# schematic_tab.net
KiCad netlist of a schematic drawn in EasyEDA
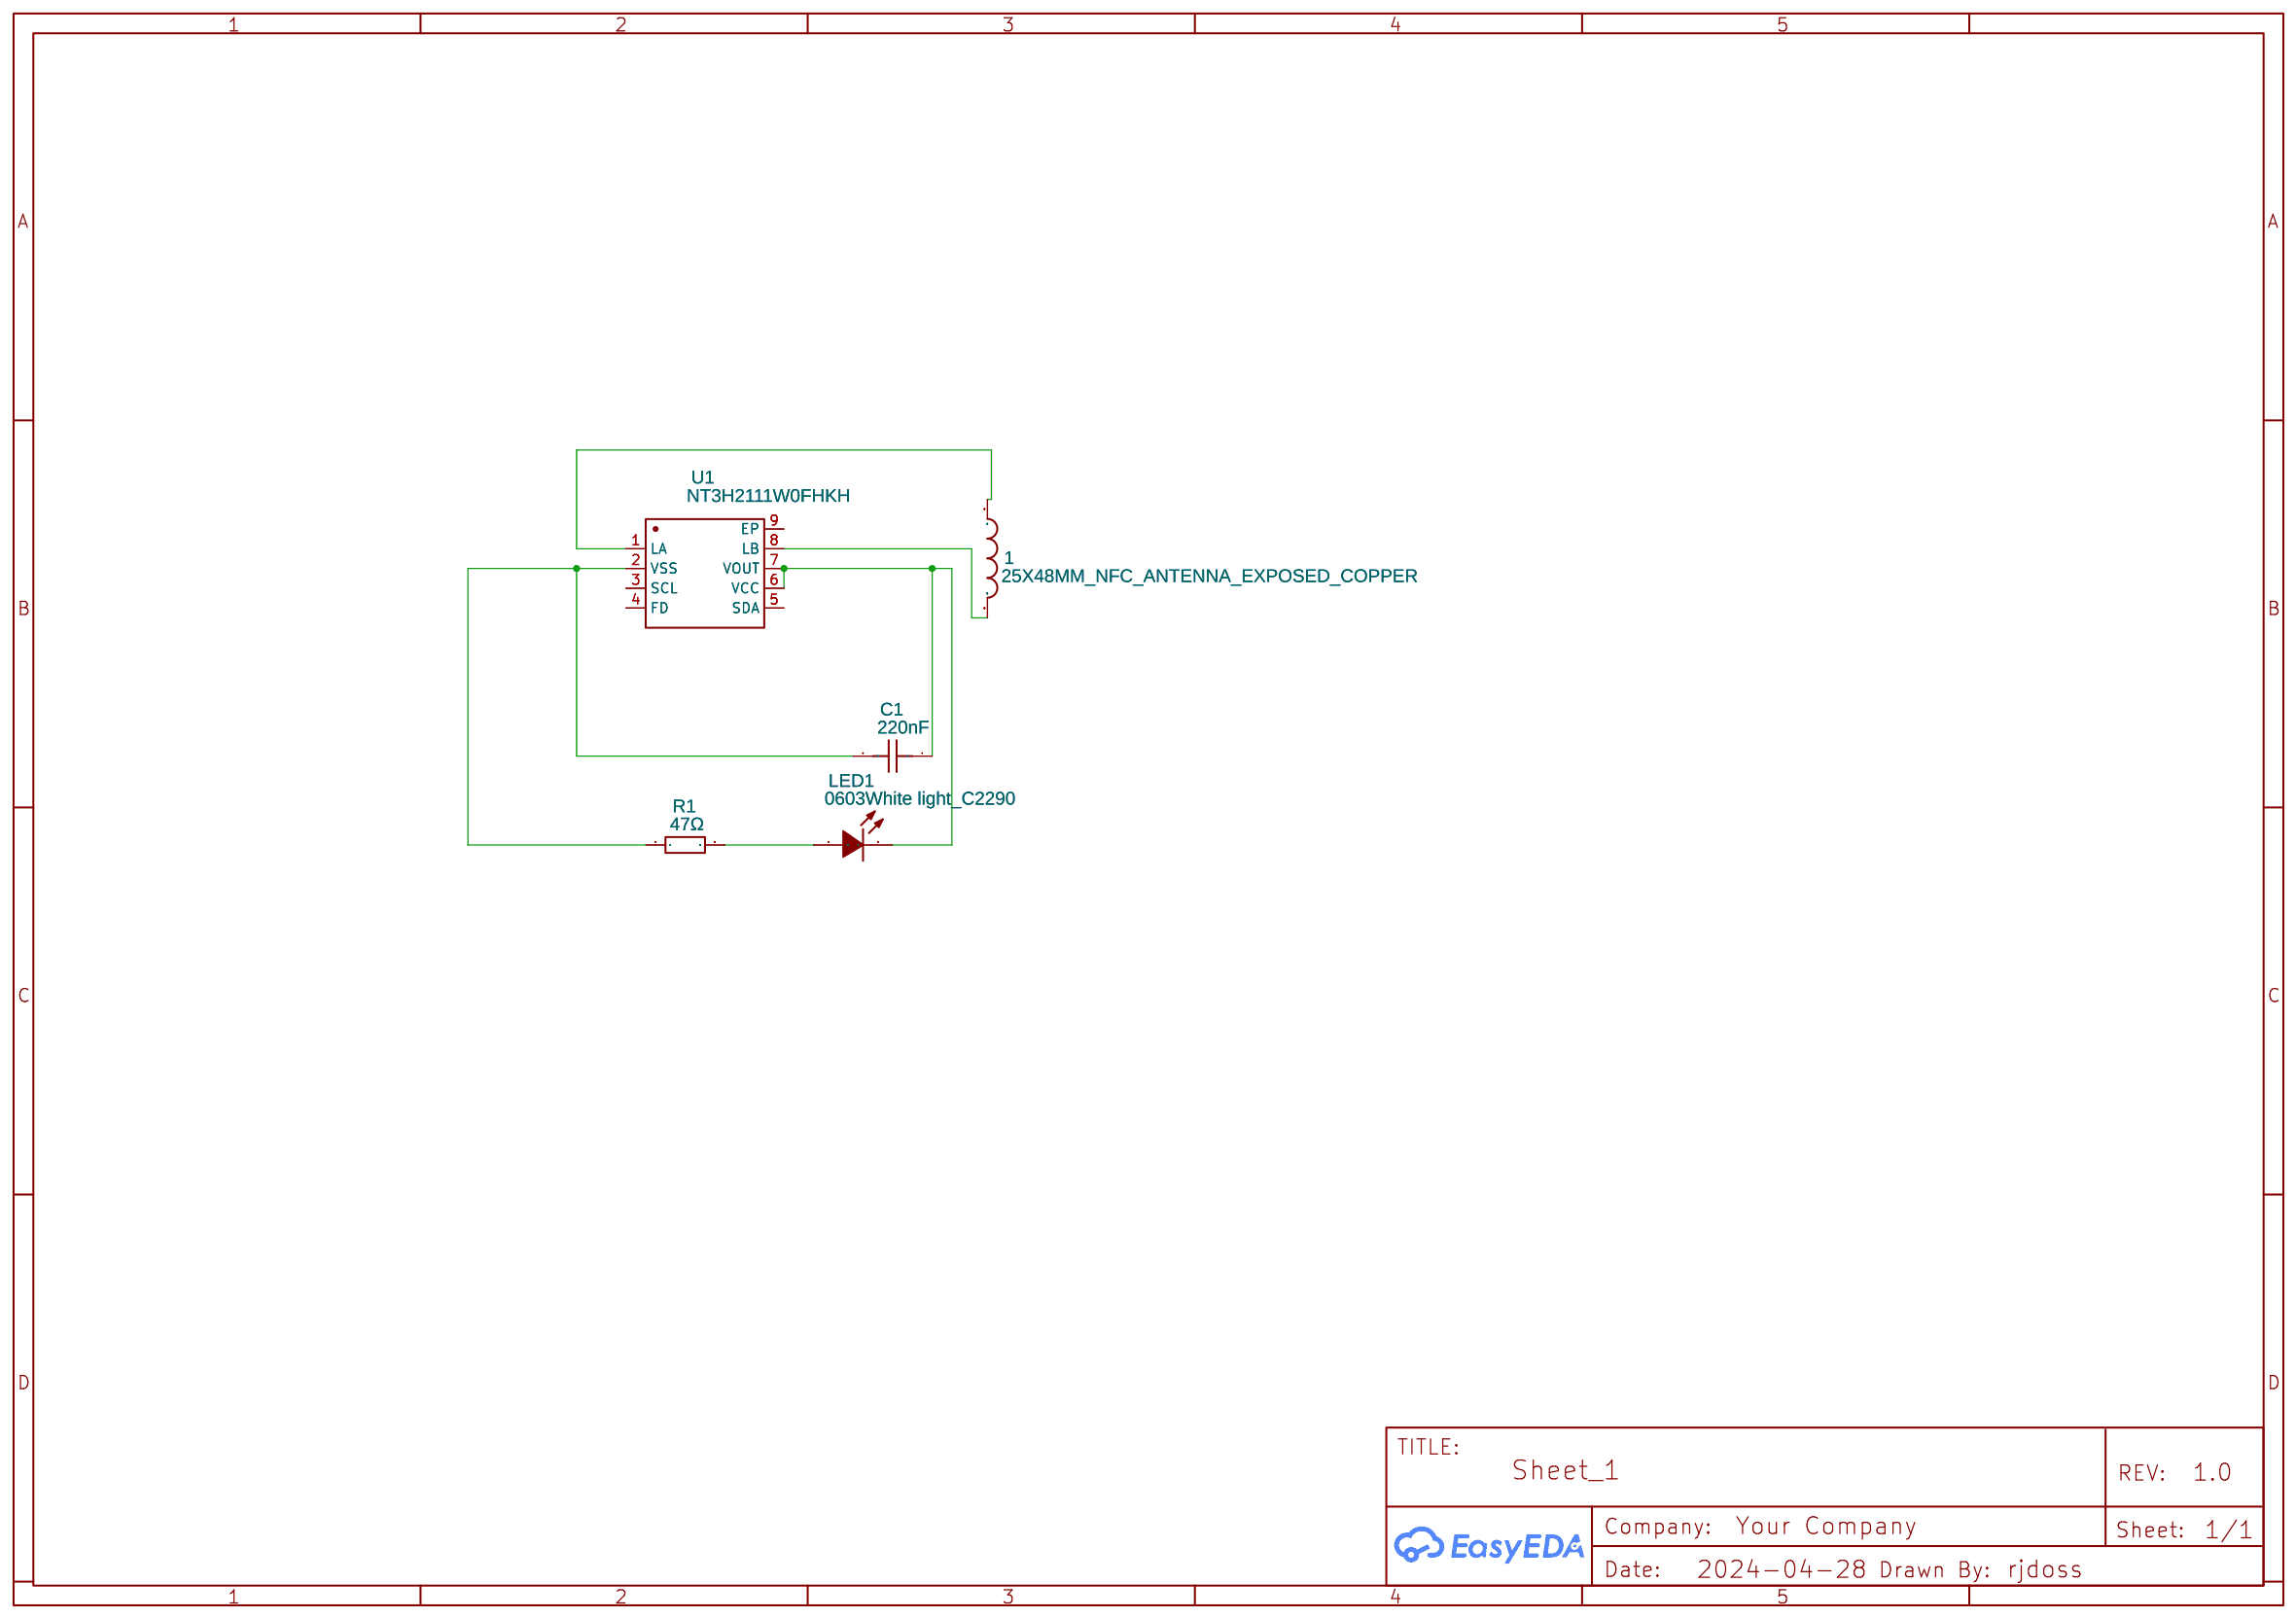
[diagram p0: schematic sheet]

(export (version "E")
  (design (tool "Eeschema 10.0.6"))
  (components
    (comp (ref "1")
      (value "25X48MM_NFC_ANTENNA_EXPOSED_COPPER")
      (libsource (lib "") (part "25X48MM_NFC_ANTENNA_EXPOSED_COPPER"))
    )
    (comp (ref "C1")
      (value "220nF")
      (fields
        (field (name "Manufacturer Part") "CL10F224ZA8NNNC")
        (field (name "Manufacturer") "SAMSUNG(三星)")
      )
      (libsource (lib "") (part "CL10F224ZA8NNNC"))
    )
    (comp (ref "LED1")
      (value "0603White light_C2290")
      (fields (field (name "Manufacturer Part") "KT-0603白灯") (field (name "Manufacturer") "KENTO"))
      (libsource (lib "") (part "0603White light_C2290"))
    )
    (comp (ref "R1")
      (value "47Ω")
      (fields
        (field (name "Manufacturer Part") "0603WAF470JT5E")
        (field (name "Manufacturer") "UNI-ROYAL(厚声)")
      )
      (libsource (lib "") (part "0603WAF470JT5E"))
    )
    (comp (ref "U1")
      (value "NT3H2111W0FHKH")
      (fields (field (name "Manufacturer") "NXP(恩智浦)"))
      (libsource (lib "") (part "NT3H2111W0FHKH"))
    )
  )
  (nets
    (net (code "1") (name "Net-(LED1-A)") (class "Default")
      (node (ref "LED1") (pin "1") (pinfunction "A_1") (pintype "unspecified"))
      (node (ref "R1") (pin "2") (pinfunction "2_2") (pintype "input"))
    )
    (net (code "2") (name "Net-(LED1-K)") (class "Default")
      (node (ref "C1") (pin "1") (pinfunction "1_1") (pintype "unspecified"))
      (node (ref "LED1") (pin "2") (pinfunction "K_2") (pintype "unspecified"))
      (node (ref "U1") (pin "6") (pinfunction "VCC_6") (pintype "unspecified"))
      (node (ref "U1") (pin "7") (pinfunction "VOUT_7") (pintype "unspecified"))
    )
    (net (code "3") (name "Net-(U1-LA)") (class "Default")
      (node (ref "1") (pin "P$1") (pinfunction "P$1_P$1") (pintype "bidirectional"))
      (node (ref "U1") (pin "1") (pinfunction "LA_1") (pintype "unspecified"))
    )
    (net (code "4") (name "Net-(U1-LB)") (class "Default")
      (node (ref "1") (pin "P$2") (pinfunction "P$2_P$2") (pintype "bidirectional"))
      (node (ref "U1") (pin "8") (pinfunction "LB_8") (pintype "unspecified"))
    )
    (net (code "5") (name "Net-(U1-VSS)") (class "Default")
      (node (ref "C1") (pin "2") (pinfunction "2_2") (pintype "unspecified"))
      (node (ref "R1") (pin "1") (pinfunction "1_1") (pintype "input"))
      (node (ref "U1") (pin "2") (pinfunction "VSS_2") (pintype "unspecified"))
    )
    (net (code "6") (name "unconnected-(U1-EP-Pad9)") (class "Default")
      (node (ref "U1") (pin "9") (pinfunction "EP_9") (pintype "unspecified"))
    )
    (net (code "7") (name "unconnected-(U1-FD-Pad4)") (class "Default")
      (node (ref "U1") (pin "4") (pinfunction "FD_4") (pintype "unspecified"))
    )
    (net (code "8") (name "unconnected-(U1-SCL-Pad3)") (class "Default")
      (node (ref "U1") (pin "3") (pinfunction "SCL_3") (pintype "unspecified"))
    )
    (net (code "9") (name "unconnected-(U1-SDA-Pad5)") (class "Default")
      (node (ref "U1") (pin "5") (pinfunction "SDA_5") (pintype "unspecified"))
    )
  )
)
